# Connectors.net
KiCad netlist of a schematic drawn in Altium Designer
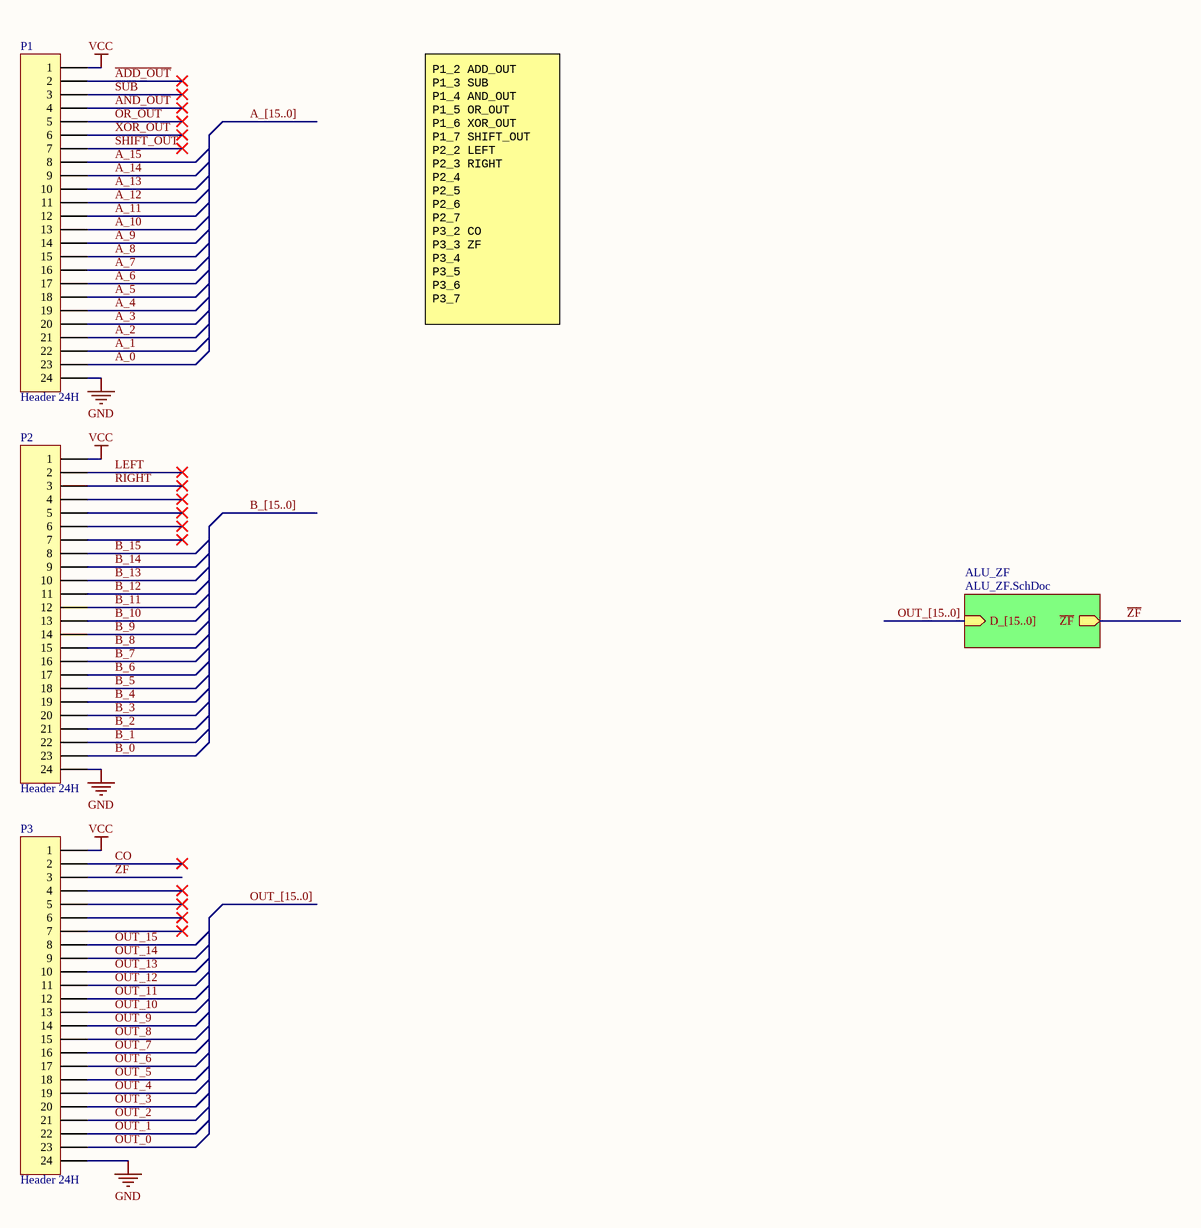
[diagram p0: Connectors.SchDoc]

(export (version "E")
  (design (tool "Eeschema 10.0.6"))
  (components
    (comp (ref "P1")
      (value "Header 24H")
      (footprint "HDR1X24H")
      (description "Header, 24-Pin, Right Angle")
      (fields (field (name "PUBLISHER") "Altium Limited"))
      (libsource (lib "Miscellaneous Connectors") (part "Header 24H"))
    )
    (comp (ref "P2")
      (value "Header 24H")
      (footprint "HDR1X24H")
      (description "Header, 24-Pin, Right Angle")
      (fields (field (name "PUBLISHER") "Altium Limited"))
      (libsource (lib "Miscellaneous Connectors") (part "Header 24H"))
    )
    (comp (ref "P3")
      (value "Header 24H")
      (footprint "HDR1X24H")
      (description "Header, 24-Pin, Right Angle")
      (fields (field (name "PUBLISHER") "Altium Limited"))
      (libsource (lib "Miscellaneous Connectors") (part "Header 24H"))
    )
  )
  (nets
    (net (code "1") (name "/A_0") (class "Default")
      (node (ref "P1") (pin "23") (pinfunction "23_23") (pintype "passive"))
    )
    (net (code "2") (name "/A_1") (class "Default")
      (node (ref "P1") (pin "22") (pinfunction "22_22") (pintype "passive"))
    )
    (net (code "3") (name "/A_2") (class "Default")
      (node (ref "P1") (pin "21") (pinfunction "21_21") (pintype "passive"))
    )
    (net (code "4") (name "/A_3") (class "Default")
      (node (ref "P1") (pin "20") (pinfunction "20_20") (pintype "passive"))
    )
    (net (code "5") (name "/A_4") (class "Default")
      (node (ref "P1") (pin "19") (pinfunction "19_19") (pintype "passive"))
    )
    (net (code "6") (name "/A_5") (class "Default")
      (node (ref "P1") (pin "18") (pinfunction "18_18") (pintype "passive"))
    )
    (net (code "7") (name "/A_6") (class "Default")
      (node (ref "P1") (pin "17") (pinfunction "17_17") (pintype "passive"))
    )
    (net (code "8") (name "/A_7") (class "Default")
      (node (ref "P1") (pin "16") (pinfunction "16_16") (pintype "passive"))
    )
    (net (code "9") (name "/A_8") (class "Default")
      (node (ref "P1") (pin "15") (pinfunction "15_15") (pintype "passive"))
    )
    (net (code "10") (name "/A_9") (class "Default")
      (node (ref "P1") (pin "14") (pinfunction "14_14") (pintype "passive"))
    )
    (net (code "11") (name "/A_10") (class "Default")
      (node (ref "P1") (pin "13") (pinfunction "13_13") (pintype "passive"))
    )
    (net (code "12") (name "/A_11") (class "Default")
      (node (ref "P1") (pin "12") (pinfunction "12_12") (pintype "passive"))
    )
    (net (code "13") (name "/A_12") (class "Default")
      (node (ref "P1") (pin "11") (pinfunction "11_11") (pintype "passive"))
    )
    (net (code "14") (name "/A_13") (class "Default")
      (node (ref "P1") (pin "10") (pinfunction "10_10") (pintype "passive"))
    )
    (net (code "15") (name "/A_14") (class "Default")
      (node (ref "P1") (pin "9") (pinfunction "9_9") (pintype "passive"))
    )
    (net (code "16") (name "/A_15") (class "Default")
      (node (ref "P1") (pin "8") (pinfunction "8_8") (pintype "passive"))
    )
    (net (code "18") (name "/B_0") (class "Default")
      (node (ref "P2") (pin "23") (pinfunction "23_23") (pintype "passive"))
    )
    (net (code "19") (name "/B_1") (class "Default")
      (node (ref "P2") (pin "22") (pinfunction "22_22") (pintype "passive"))
    )
    (net (code "20") (name "/B_2") (class "Default")
      (node (ref "P2") (pin "21") (pinfunction "21_21") (pintype "passive"))
    )
    (net (code "21") (name "/B_3") (class "Default")
      (node (ref "P2") (pin "20") (pinfunction "20_20") (pintype "passive"))
    )
    (net (code "22") (name "/B_4") (class "Default")
      (node (ref "P2") (pin "19") (pinfunction "19_19") (pintype "passive"))
    )
    (net (code "23") (name "/B_5") (class "Default")
      (node (ref "P2") (pin "18") (pinfunction "18_18") (pintype "passive"))
    )
    (net (code "24") (name "/B_6") (class "Default")
      (node (ref "P2") (pin "17") (pinfunction "17_17") (pintype "passive"))
    )
    (net (code "25") (name "/B_7") (class "Default")
      (node (ref "P2") (pin "16") (pinfunction "16_16") (pintype "passive"))
    )
    (net (code "26") (name "/B_8") (class "Default")
      (node (ref "P2") (pin "15") (pinfunction "15_15") (pintype "passive"))
    )
    (net (code "27") (name "/B_9") (class "Default")
      (node (ref "P2") (pin "14") (pinfunction "14_14") (pintype "passive"))
    )
    (net (code "28") (name "/B_10") (class "Default")
      (node (ref "P2") (pin "13") (pinfunction "13_13") (pintype "passive"))
    )
    (net (code "29") (name "/B_11") (class "Default")
      (node (ref "P2") (pin "12") (pinfunction "12_12") (pintype "passive"))
    )
    (net (code "30") (name "/B_12") (class "Default")
      (node (ref "P2") (pin "11") (pinfunction "11_11") (pintype "passive"))
    )
    (net (code "31") (name "/B_13") (class "Default")
      (node (ref "P2") (pin "10") (pinfunction "10_10") (pintype "passive"))
    )
    (net (code "32") (name "/B_14") (class "Default")
      (node (ref "P2") (pin "9") (pinfunction "9_9") (pintype "passive"))
    )
    (net (code "33") (name "/B_15") (class "Default")
      (node (ref "P2") (pin "8") (pinfunction "8_8") (pintype "passive"))
    )
    (net (code "35") (name "/CO") (class "Default")
      (node (ref "P3") (pin "2") (pinfunction "2_2") (pintype "passive+no_connect"))
    )
    (net (code "36") (name "/LEFT") (class "Default")
      (node (ref "P2") (pin "2") (pinfunction "2_2") (pintype "passive+no_connect"))
    )
    (net (code "37") (name "/OUT_0") (class "Default")
      (node (ref "P3") (pin "23") (pinfunction "23_23") (pintype "passive"))
    )
    (net (code "38") (name "/OUT_1") (class "Default")
      (node (ref "P3") (pin "22") (pinfunction "22_22") (pintype "passive"))
    )
    (net (code "39") (name "/OUT_2") (class "Default")
      (node (ref "P3") (pin "21") (pinfunction "21_21") (pintype "passive"))
    )
    (net (code "40") (name "/OUT_3") (class "Default")
      (node (ref "P3") (pin "20") (pinfunction "20_20") (pintype "passive"))
    )
    (net (code "41") (name "/OUT_4") (class "Default")
      (node (ref "P3") (pin "19") (pinfunction "19_19") (pintype "passive"))
    )
    (net (code "42") (name "/OUT_5") (class "Default")
      (node (ref "P3") (pin "18") (pinfunction "18_18") (pintype "passive"))
    )
    (net (code "43") (name "/OUT_6") (class "Default")
      (node (ref "P3") (pin "17") (pinfunction "17_17") (pintype "passive"))
    )
    (net (code "44") (name "/OUT_7") (class "Default")
      (node (ref "P3") (pin "16") (pinfunction "16_16") (pintype "passive"))
    )
    (net (code "45") (name "/OUT_8") (class "Default")
      (node (ref "P3") (pin "15") (pinfunction "15_15") (pintype "passive"))
    )
    (net (code "46") (name "/OUT_9") (class "Default")
      (node (ref "P3") (pin "14") (pinfunction "14_14") (pintype "passive"))
    )
    (net (code "47") (name "/OUT_10") (class "Default")
      (node (ref "P3") (pin "13") (pinfunction "13_13") (pintype "passive"))
    )
    (net (code "48") (name "/OUT_11") (class "Default")
      (node (ref "P3") (pin "12") (pinfunction "12_12") (pintype "passive"))
    )
    (net (code "49") (name "/OUT_12") (class "Default")
      (node (ref "P3") (pin "11") (pinfunction "11_11") (pintype "passive"))
    )
    (net (code "50") (name "/OUT_13") (class "Default")
      (node (ref "P3") (pin "10") (pinfunction "10_10") (pintype "passive"))
    )
    (net (code "51") (name "/OUT_14") (class "Default")
      (node (ref "P3") (pin "9") (pinfunction "9_9") (pintype "passive"))
    )
    (net (code "52") (name "/OUT_15") (class "Default")
      (node (ref "P3") (pin "8") (pinfunction "8_8") (pintype "passive"))
    )
    (net (code "54") (name "/RIGHT") (class "Default")
      (node (ref "P2") (pin "3") (pinfunction "3_3") (pintype "passive+no_connect"))
    )
    (net (code "55") (name "/SUB") (class "Default")
      (node (ref "P1") (pin "3") (pinfunction "3_3") (pintype "passive+no_connect"))
    )
    (net (code "56") (name "/~{ADD_OUT}") (class "Default")
      (node (ref "P1") (pin "2") (pinfunction "2_2") (pintype "passive+no_connect"))
    )
    (net (code "57") (name "/~{AND_OUT}") (class "Default")
      (node (ref "P1") (pin "4") (pinfunction "4_4") (pintype "passive+no_connect"))
    )
    (net (code "58") (name "/~{OR_OUT}") (class "Default")
      (node (ref "P1") (pin "5") (pinfunction "5_5") (pintype "passive+no_connect"))
    )
    (net (code "59") (name "/~{SHIFT_OUT}") (class "Default")
      (node (ref "P1") (pin "7") (pinfunction "7_7") (pintype "passive+no_connect"))
    )
    (net (code "60") (name "/~{XOR_OUT}") (class "Default")
      (node (ref "P1") (pin "6") (pinfunction "6_6") (pintype "passive+no_connect"))
    )
    (net (code "61") (name "/~{ZF}") (class "Default")
      (node (ref "P3") (pin "3") (pinfunction "3_3") (pintype "passive"))
    )
    (net (code "62") (name "GND") (class "Default")
      (node (ref "P1") (pin "24") (pinfunction "24_24") (pintype "passive"))
      (node (ref "P2") (pin "24") (pinfunction "24_24") (pintype "passive"))
      (node (ref "P3") (pin "24") (pinfunction "24_24") (pintype "passive"))
    )
    (net (code "63") (name "VCC") (class "Default")
      (node (ref "P1") (pin "1") (pinfunction "1_1") (pintype "passive"))
      (node (ref "P2") (pin "1") (pinfunction "1_1") (pintype "passive"))
      (node (ref "P3") (pin "1") (pinfunction "1_1") (pintype "passive"))
    )
    (net (code "64") (name "unconnected-(P2-Pad4)") (class "Default")
      (node (ref "P2") (pin "4") (pinfunction "4_4") (pintype "passive+no_connect"))
    )
    (net (code "65") (name "unconnected-(P2-Pad5)") (class "Default")
      (node (ref "P2") (pin "5") (pinfunction "5_5") (pintype "passive+no_connect"))
    )
    (net (code "66") (name "unconnected-(P2-Pad6)") (class "Default")
      (node (ref "P2") (pin "6") (pinfunction "6_6") (pintype "passive+no_connect"))
    )
    (net (code "67") (name "unconnected-(P2-Pad7)") (class "Default")
      (node (ref "P2") (pin "7") (pinfunction "7_7") (pintype "passive+no_connect"))
    )
    (net (code "68") (name "unconnected-(P3-Pad4)") (class "Default")
      (node (ref "P3") (pin "4") (pinfunction "4_4") (pintype "passive+no_connect"))
    )
    (net (code "69") (name "unconnected-(P3-Pad5)") (class "Default")
      (node (ref "P3") (pin "5") (pinfunction "5_5") (pintype "passive+no_connect"))
    )
    (net (code "70") (name "unconnected-(P3-Pad6)") (class "Default")
      (node (ref "P3") (pin "6") (pinfunction "6_6") (pintype "passive+no_connect"))
    )
    (net (code "71") (name "unconnected-(P3-Pad7)") (class "Default")
      (node (ref "P3") (pin "7") (pinfunction "7_7") (pintype "passive+no_connect"))
    )
  )
)
